# LED-mini20-SHIM.net
KiCad netlist of a schematic drawn in EAGLE
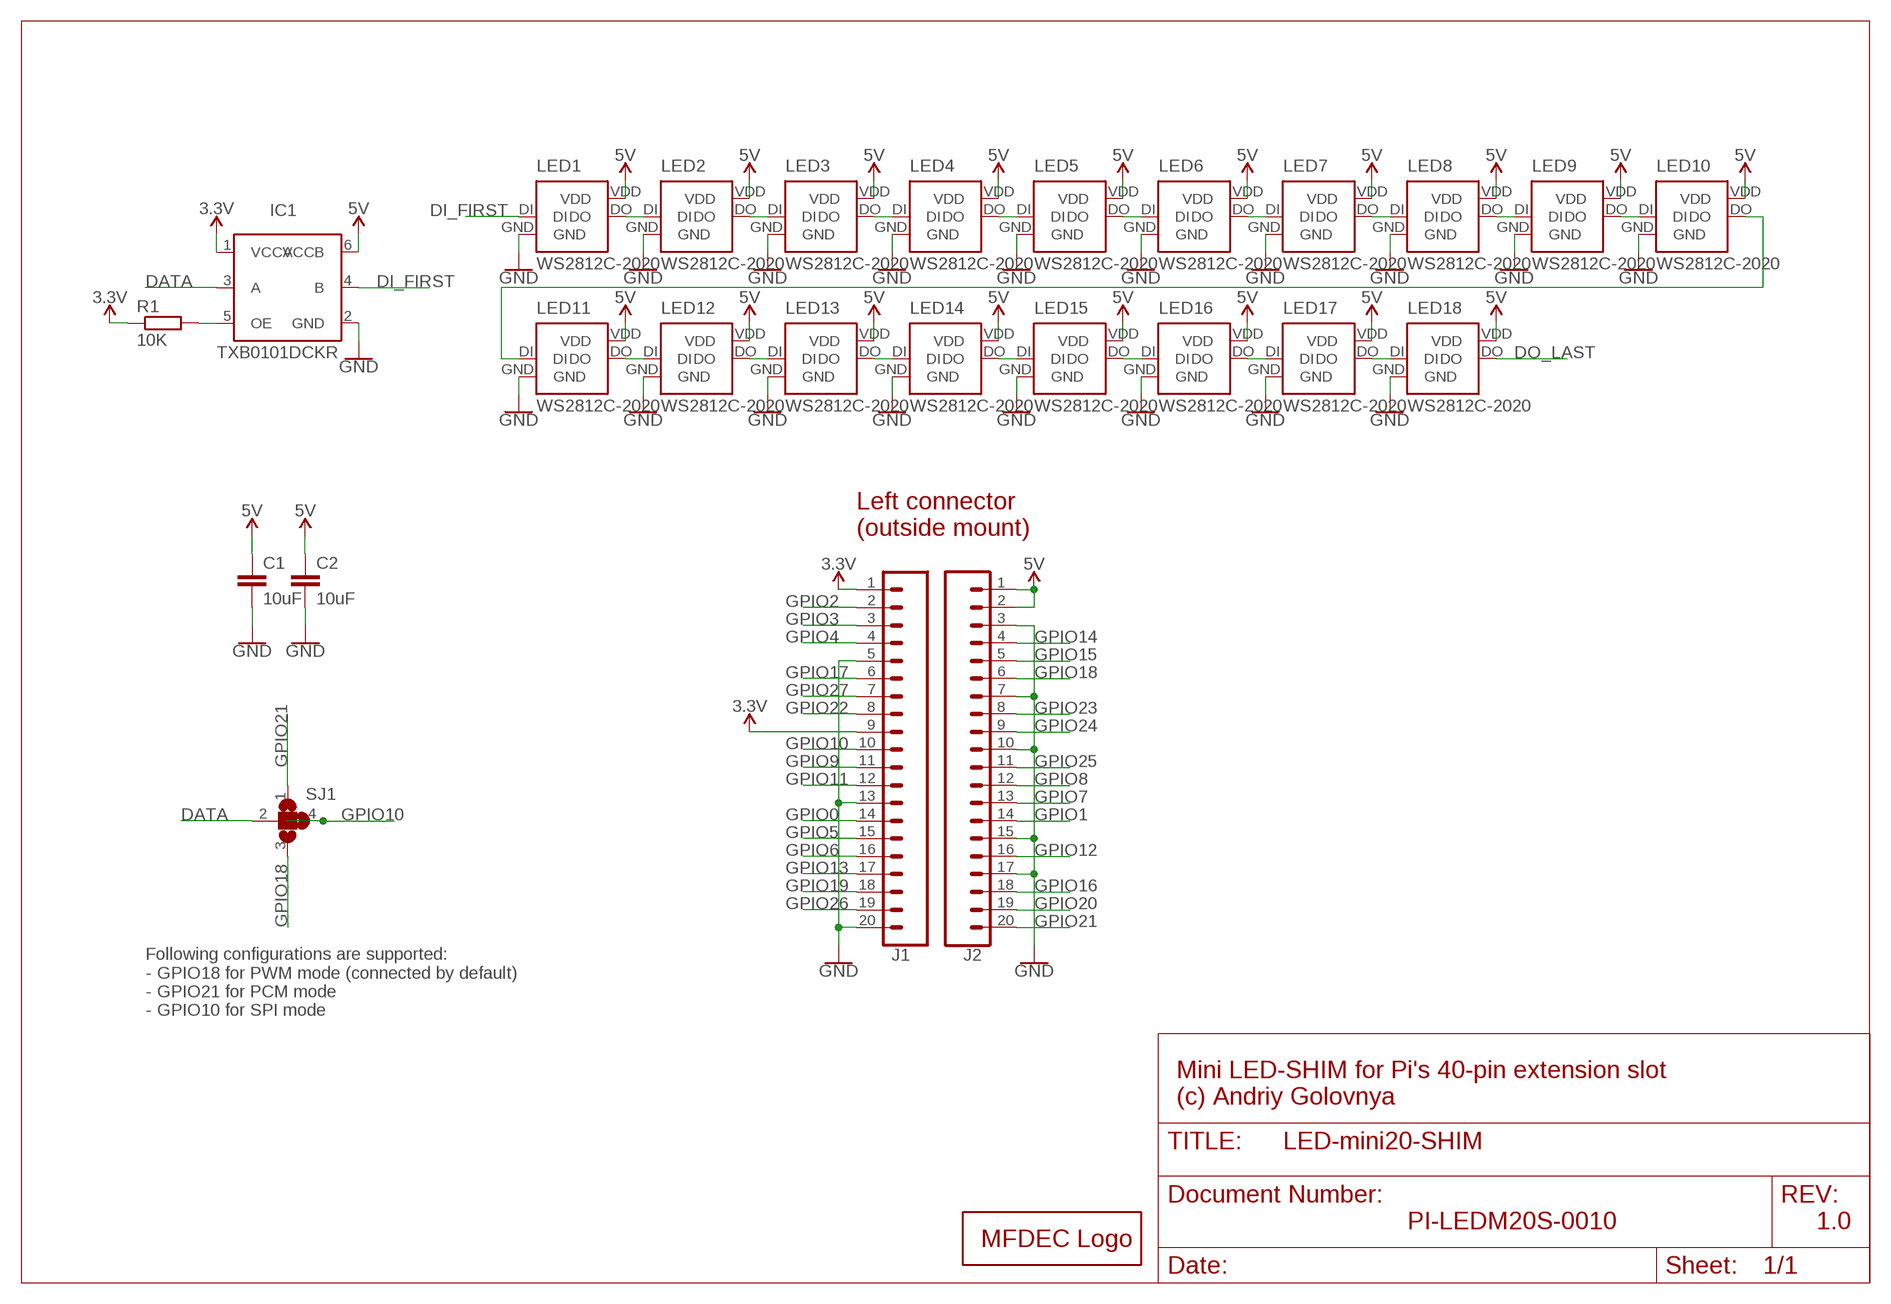
[diagram p0: schematic, sheet 1]

(export (version "E")
  (design (tool "Eeschema 10.0.6"))
  (components
    (comp (ref "C1")
      (value "10uF")
      (footprint "eagle-import:C0805")
      (libsource (lib "eagle-import") (part "C-EUC0805"))
    )
    (comp (ref "C2")
      (value "10uF")
      (footprint "eagle-import:C0805")
      (libsource (lib "eagle-import") (part "C-EUC0805"))
    )
    (comp (ref "IC1")
      (value "TXB0101DCKR")
      (footprint "eagle-import:SOT65P210X110-6N")
      (libsource (lib "eagle-import") (part "TXB0101DCKR"))
    )
    (comp (ref "J1")
      (value "CONN_20LOCK")
      (footprint "eagle-import:1X20_LOCK")
      (libsource (lib "eagle-import") (part "CONN_20LOCK"))
    )
    (comp (ref "J2")
      (value "CONN_20LOCK")
      (footprint "eagle-import:1X20_LOCK")
      (libsource (lib "eagle-import") (part "CONN_20LOCK"))
    )
    (comp (ref "LED1")
      (value "WS2812C-2020")
      (footprint "eagle-import:WS2812X-2020")
      (libsource (lib "eagle-import") (part "WS2812C-2020"))
    )
    (comp (ref "LED2")
      (value "WS2812C-2020")
      (footprint "eagle-import:WS2812X-2020")
      (libsource (lib "eagle-import") (part "WS2812C-2020"))
    )
    (comp (ref "LED3")
      (value "WS2812C-2020")
      (footprint "eagle-import:WS2812X-2020")
      (libsource (lib "eagle-import") (part "WS2812C-2020"))
    )
    (comp (ref "LED4")
      (value "WS2812C-2020")
      (footprint "eagle-import:WS2812X-2020")
      (libsource (lib "eagle-import") (part "WS2812C-2020"))
    )
    (comp (ref "LED5")
      (value "WS2812C-2020")
      (footprint "eagle-import:WS2812X-2020")
      (libsource (lib "eagle-import") (part "WS2812C-2020"))
    )
    (comp (ref "LED6")
      (value "WS2812C-2020")
      (footprint "eagle-import:WS2812X-2020")
      (libsource (lib "eagle-import") (part "WS2812C-2020"))
    )
    (comp (ref "LED7")
      (value "WS2812C-2020")
      (footprint "eagle-import:WS2812X-2020")
      (libsource (lib "eagle-import") (part "WS2812C-2020"))
    )
    (comp (ref "LED8")
      (value "WS2812C-2020")
      (footprint "eagle-import:WS2812X-2020")
      (libsource (lib "eagle-import") (part "WS2812C-2020"))
    )
    (comp (ref "LED9")
      (value "WS2812C-2020")
      (footprint "eagle-import:WS2812X-2020")
      (libsource (lib "eagle-import") (part "WS2812C-2020"))
    )
    (comp (ref "LED10")
      (value "WS2812C-2020")
      (footprint "eagle-import:WS2812X-2020")
      (libsource (lib "eagle-import") (part "WS2812C-2020"))
    )
    (comp (ref "LED11")
      (value "WS2812C-2020")
      (footprint "eagle-import:WS2812X-2020")
      (libsource (lib "eagle-import") (part "WS2812C-2020"))
    )
    (comp (ref "LED12")
      (value "WS2812C-2020")
      (footprint "eagle-import:WS2812X-2020")
      (libsource (lib "eagle-import") (part "WS2812C-2020"))
    )
    (comp (ref "LED13")
      (value "WS2812C-2020")
      (footprint "eagle-import:WS2812X-2020")
      (libsource (lib "eagle-import") (part "WS2812C-2020"))
    )
    (comp (ref "LED14")
      (value "WS2812C-2020")
      (footprint "eagle-import:WS2812X-2020")
      (libsource (lib "eagle-import") (part "WS2812C-2020"))
    )
    (comp (ref "LED15")
      (value "WS2812C-2020")
      (footprint "eagle-import:WS2812X-2020")
      (libsource (lib "eagle-import") (part "WS2812C-2020"))
    )
    (comp (ref "LED16")
      (value "WS2812C-2020")
      (footprint "eagle-import:WS2812X-2020")
      (libsource (lib "eagle-import") (part "WS2812C-2020"))
    )
    (comp (ref "LED17")
      (value "WS2812C-2020")
      (footprint "eagle-import:WS2812X-2020")
      (libsource (lib "eagle-import") (part "WS2812C-2020"))
    )
    (comp (ref "LED18")
      (value "WS2812C-2020")
      (footprint "eagle-import:WS2812X-2020")
      (libsource (lib "eagle-import") (part "WS2812C-2020"))
    )
    (comp (ref "LOGO1")
      (value "MFDECLOGO_L_10MM")
      (footprint "eagle-import:MFDEC_L_10MM")
      (libsource (lib "eagle-import") (part "MFDECLOGO_L_10MM"))
    )
    (comp (ref "R1")
      (value "10K")
      (footprint "eagle-import:R0402")
      (libsource (lib "eagle-import") (part "R-EU_R0402"))
    )
    (comp (ref "SJ1")
      (value "SJ3")
      (footprint "eagle-import:SJ_3")
      (libsource (lib "eagle-import") (part "SJ3"))
    )
  )
  (nets
    (net (code "1") (name "/DATA") (class "Default")
      (node (ref "IC1") (pin "3") (pinfunction "A_3") (pintype "bidirectional"))
      (node (ref "SJ1") (pin "2") (pinfunction "2_2") (pintype "passive"))
    )
    (net (code "2") (name "/DI_FIRST") (class "Default")
      (node (ref "IC1") (pin "4") (pinfunction "B_4") (pintype "bidirectional"))
      (node (ref "LED1") (pin "DI") (pinfunction "DI_DI") (pintype "input"))
    )
    (net (code "3") (name "/DO_LAST") (class "Default")
      (node (ref "LED18") (pin "DO") (pinfunction "DO_DO") (pintype "output"))
    )
    (net (code "4") (name "/GPIO0") (class "Default")
      (node (ref "J1") (pin "14") (pinfunction "14_14") (pintype "passive"))
    )
    (net (code "5") (name "/GPIO1") (class "Default")
      (node (ref "J2") (pin "14") (pinfunction "14_14") (pintype "passive"))
    )
    (net (code "6") (name "/GPIO2") (class "Default")
      (node (ref "J1") (pin "2") (pinfunction "2_2") (pintype "passive"))
    )
    (net (code "7") (name "/GPIO3") (class "Default")
      (node (ref "J1") (pin "3") (pinfunction "3_3") (pintype "passive"))
    )
    (net (code "8") (name "/GPIO4") (class "Default")
      (node (ref "J1") (pin "4") (pinfunction "4_4") (pintype "passive"))
    )
    (net (code "9") (name "/GPIO5") (class "Default")
      (node (ref "J1") (pin "15") (pinfunction "15_15") (pintype "passive"))
    )
    (net (code "10") (name "/GPIO6") (class "Default")
      (node (ref "J1") (pin "16") (pinfunction "16_16") (pintype "passive"))
    )
    (net (code "11") (name "/GPIO7") (class "Default")
      (node (ref "J2") (pin "13") (pinfunction "13_13") (pintype "passive"))
    )
    (net (code "12") (name "/GPIO8") (class "Default")
      (node (ref "J2") (pin "12") (pinfunction "12_12") (pintype "passive"))
    )
    (net (code "13") (name "/GPIO9") (class "Default")
      (node (ref "J1") (pin "11") (pinfunction "11_11") (pintype "passive"))
    )
    (net (code "14") (name "/GPIO10") (class "Default")
      (node (ref "J1") (pin "10") (pinfunction "10_10") (pintype "passive"))
      (node (ref "SJ1") (pin "4") (pinfunction "4_4") (pintype "passive"))
    )
    (net (code "15") (name "/GPIO11") (class "Default")
      (node (ref "J1") (pin "12") (pinfunction "12_12") (pintype "passive"))
    )
    (net (code "16") (name "/GPIO12") (class "Default")
      (node (ref "J2") (pin "16") (pinfunction "16_16") (pintype "passive"))
    )
    (net (code "17") (name "/GPIO13") (class "Default")
      (node (ref "J1") (pin "17") (pinfunction "17_17") (pintype "passive"))
    )
    (net (code "18") (name "/GPIO14") (class "Default")
      (node (ref "J2") (pin "4") (pinfunction "4_4") (pintype "passive"))
    )
    (net (code "19") (name "/GPIO15") (class "Default")
      (node (ref "J2") (pin "5") (pinfunction "5_5") (pintype "passive"))
    )
    (net (code "20") (name "/GPIO16") (class "Default")
      (node (ref "J2") (pin "18") (pinfunction "18_18") (pintype "passive"))
    )
    (net (code "21") (name "/GPIO17") (class "Default")
      (node (ref "J1") (pin "6") (pinfunction "6_6") (pintype "passive"))
    )
    (net (code "22") (name "/GPIO18") (class "Default")
      (node (ref "J2") (pin "6") (pinfunction "6_6") (pintype "passive"))
      (node (ref "SJ1") (pin "3") (pinfunction "3_3") (pintype "passive"))
    )
    (net (code "23") (name "/GPIO19") (class "Default")
      (node (ref "J1") (pin "18") (pinfunction "18_18") (pintype "passive"))
    )
    (net (code "24") (name "/GPIO20") (class "Default")
      (node (ref "J2") (pin "19") (pinfunction "19_19") (pintype "passive"))
    )
    (net (code "25") (name "/GPIO21") (class "Default")
      (node (ref "J2") (pin "20") (pinfunction "20_20") (pintype "passive"))
      (node (ref "SJ1") (pin "1") (pinfunction "1_1") (pintype "passive"))
    )
    (net (code "26") (name "/GPIO22") (class "Default")
      (node (ref "J1") (pin "8") (pinfunction "8_8") (pintype "passive"))
    )
    (net (code "27") (name "/GPIO23") (class "Default")
      (node (ref "J2") (pin "8") (pinfunction "8_8") (pintype "passive"))
    )
    (net (code "28") (name "/GPIO24") (class "Default")
      (node (ref "J2") (pin "9") (pinfunction "9_9") (pintype "passive"))
    )
    (net (code "29") (name "/GPIO25") (class "Default")
      (node (ref "J2") (pin "11") (pinfunction "11_11") (pintype "passive"))
    )
    (net (code "30") (name "/GPIO26") (class "Default")
      (node (ref "J1") (pin "19") (pinfunction "19_19") (pintype "passive"))
    )
    (net (code "31") (name "/GPIO27") (class "Default")
      (node (ref "J1") (pin "7") (pinfunction "7_7") (pintype "passive"))
    )
    (net (code "32") (name "3.3V") (class "Default")
      (node (ref "IC1") (pin "1") (pinfunction "VCCA_1") (pintype "power_in"))
      (node (ref "J1") (pin "1") (pinfunction "1_1") (pintype "passive"))
      (node (ref "J1") (pin "9") (pinfunction "9_9") (pintype "passive"))
      (node (ref "R1") (pin "1") (pinfunction "1_1") (pintype "passive"))
    )
    (net (code "33") (name "5V") (class "Default")
      (node (ref "C1") (pin "1") (pinfunction "1_1") (pintype "passive"))
      (node (ref "C2") (pin "1") (pinfunction "1_1") (pintype "passive"))
      (node (ref "IC1") (pin "6") (pinfunction "VCCB_6") (pintype "power_in"))
      (node (ref "J2") (pin "1") (pinfunction "1_1") (pintype "passive"))
      (node (ref "J2") (pin "2") (pinfunction "2_2") (pintype "passive"))
      (node (ref "LED1") (pin "VDD") (pinfunction "VDD_VDD") (pintype "power_in"))
      (node (ref "LED10") (pin "VDD") (pinfunction "VDD_VDD") (pintype "power_in"))
      (node (ref "LED11") (pin "VDD") (pinfunction "VDD_VDD") (pintype "power_in"))
      (node (ref "LED12") (pin "VDD") (pinfunction "VDD_VDD") (pintype "power_in"))
      (node (ref "LED13") (pin "VDD") (pinfunction "VDD_VDD") (pintype "power_in"))
      (node (ref "LED14") (pin "VDD") (pinfunction "VDD_VDD") (pintype "power_in"))
      (node (ref "LED15") (pin "VDD") (pinfunction "VDD_VDD") (pintype "power_in"))
      (node (ref "LED16") (pin "VDD") (pinfunction "VDD_VDD") (pintype "power_in"))
      (node (ref "LED17") (pin "VDD") (pinfunction "VDD_VDD") (pintype "power_in"))
      (node (ref "LED18") (pin "VDD") (pinfunction "VDD_VDD") (pintype "power_in"))
      (node (ref "LED2") (pin "VDD") (pinfunction "VDD_VDD") (pintype "power_in"))
      (node (ref "LED3") (pin "VDD") (pinfunction "VDD_VDD") (pintype "power_in"))
      (node (ref "LED4") (pin "VDD") (pinfunction "VDD_VDD") (pintype "power_in"))
      (node (ref "LED5") (pin "VDD") (pinfunction "VDD_VDD") (pintype "power_in"))
      (node (ref "LED6") (pin "VDD") (pinfunction "VDD_VDD") (pintype "power_in"))
      (node (ref "LED7") (pin "VDD") (pinfunction "VDD_VDD") (pintype "power_in"))
      (node (ref "LED8") (pin "VDD") (pinfunction "VDD_VDD") (pintype "power_in"))
      (node (ref "LED9") (pin "VDD") (pinfunction "VDD_VDD") (pintype "power_in"))
    )
    (net (code "34") (name "GND") (class "Default")
      (node (ref "C1") (pin "2") (pinfunction "2_2") (pintype "passive"))
      (node (ref "C2") (pin "2") (pinfunction "2_2") (pintype "passive"))
      (node (ref "IC1") (pin "2") (pinfunction "GND_2") (pintype "power_in"))
      (node (ref "J1") (pin "13") (pinfunction "13_13") (pintype "passive"))
      (node (ref "J1") (pin "20") (pinfunction "20_20") (pintype "passive"))
      (node (ref "J1") (pin "5") (pinfunction "5_5") (pintype "passive"))
      (node (ref "J2") (pin "10") (pinfunction "10_10") (pintype "passive"))
      (node (ref "J2") (pin "15") (pinfunction "15_15") (pintype "passive"))
      (node (ref "J2") (pin "17") (pinfunction "17_17") (pintype "passive"))
      (node (ref "J2") (pin "3") (pinfunction "3_3") (pintype "passive"))
      (node (ref "J2") (pin "7") (pinfunction "7_7") (pintype "passive"))
      (node (ref "LED1") (pin "GND") (pinfunction "GND_GND") (pintype "power_in"))
      (node (ref "LED10") (pin "GND") (pinfunction "GND_GND") (pintype "power_in"))
      (node (ref "LED11") (pin "GND") (pinfunction "GND_GND") (pintype "power_in"))
      (node (ref "LED12") (pin "GND") (pinfunction "GND_GND") (pintype "power_in"))
      (node (ref "LED13") (pin "GND") (pinfunction "GND_GND") (pintype "power_in"))
      (node (ref "LED14") (pin "GND") (pinfunction "GND_GND") (pintype "power_in"))
      (node (ref "LED15") (pin "GND") (pinfunction "GND_GND") (pintype "power_in"))
      (node (ref "LED16") (pin "GND") (pinfunction "GND_GND") (pintype "power_in"))
      (node (ref "LED17") (pin "GND") (pinfunction "GND_GND") (pintype "power_in"))
      (node (ref "LED18") (pin "GND") (pinfunction "GND_GND") (pintype "power_in"))
      (node (ref "LED2") (pin "GND") (pinfunction "GND_GND") (pintype "power_in"))
      (node (ref "LED3") (pin "GND") (pinfunction "GND_GND") (pintype "power_in"))
      (node (ref "LED4") (pin "GND") (pinfunction "GND_GND") (pintype "power_in"))
      (node (ref "LED5") (pin "GND") (pinfunction "GND_GND") (pintype "power_in"))
      (node (ref "LED6") (pin "GND") (pinfunction "GND_GND") (pintype "power_in"))
      (node (ref "LED7") (pin "GND") (pinfunction "GND_GND") (pintype "power_in"))
      (node (ref "LED8") (pin "GND") (pinfunction "GND_GND") (pintype "power_in"))
      (node (ref "LED9") (pin "GND") (pinfunction "GND_GND") (pintype "power_in"))
    )
    (net (code "35") (name "Net-(IC1-OE)") (class "Default")
      (node (ref "IC1") (pin "5") (pinfunction "OE_5") (pintype "input"))
      (node (ref "R1") (pin "2") (pinfunction "2_2") (pintype "passive"))
    )
    (net (code "36") (name "Net-(LED1-PadDO)") (class "Default")
      (node (ref "LED1") (pin "DO") (pinfunction "DO_DO") (pintype "output"))
      (node (ref "LED2") (pin "DI") (pinfunction "DI_DI") (pintype "input"))
    )
    (net (code "37") (name "Net-(LED2-PadDO)") (class "Default")
      (node (ref "LED2") (pin "DO") (pinfunction "DO_DO") (pintype "output"))
      (node (ref "LED3") (pin "DI") (pinfunction "DI_DI") (pintype "input"))
    )
    (net (code "38") (name "Net-(LED3-PadDO)") (class "Default")
      (node (ref "LED3") (pin "DO") (pinfunction "DO_DO") (pintype "output"))
      (node (ref "LED4") (pin "DI") (pinfunction "DI_DI") (pintype "input"))
    )
    (net (code "39") (name "Net-(LED4-PadDO)") (class "Default")
      (node (ref "LED4") (pin "DO") (pinfunction "DO_DO") (pintype "output"))
      (node (ref "LED5") (pin "DI") (pinfunction "DI_DI") (pintype "input"))
    )
    (net (code "40") (name "Net-(LED5-PadDO)") (class "Default")
      (node (ref "LED5") (pin "DO") (pinfunction "DO_DO") (pintype "output"))
      (node (ref "LED6") (pin "DI") (pinfunction "DI_DI") (pintype "input"))
    )
    (net (code "41") (name "Net-(LED6-PadDO)") (class "Default")
      (node (ref "LED6") (pin "DO") (pinfunction "DO_DO") (pintype "output"))
      (node (ref "LED7") (pin "DI") (pinfunction "DI_DI") (pintype "input"))
    )
    (net (code "42") (name "Net-(LED7-PadDO)") (class "Default")
      (node (ref "LED7") (pin "DO") (pinfunction "DO_DO") (pintype "output"))
      (node (ref "LED8") (pin "DI") (pinfunction "DI_DI") (pintype "input"))
    )
    (net (code "43") (name "Net-(LED8-PadDO)") (class "Default")
      (node (ref "LED8") (pin "DO") (pinfunction "DO_DO") (pintype "output"))
      (node (ref "LED9") (pin "DI") (pinfunction "DI_DI") (pintype "input"))
    )
    (net (code "44") (name "Net-(LED10-PadDI)") (class "Default")
      (node (ref "LED10") (pin "DI") (pinfunction "DI_DI") (pintype "input"))
      (node (ref "LED9") (pin "DO") (pinfunction "DO_DO") (pintype "output"))
    )
    (net (code "45") (name "Net-(LED10-PadDO)") (class "Default")
      (node (ref "LED10") (pin "DO") (pinfunction "DO_DO") (pintype "output"))
      (node (ref "LED11") (pin "DI") (pinfunction "DI_DI") (pintype "input"))
    )
    (net (code "46") (name "Net-(LED11-PadDO)") (class "Default")
      (node (ref "LED11") (pin "DO") (pinfunction "DO_DO") (pintype "output"))
      (node (ref "LED12") (pin "DI") (pinfunction "DI_DI") (pintype "input"))
    )
    (net (code "47") (name "Net-(LED12-PadDO)") (class "Default")
      (node (ref "LED12") (pin "DO") (pinfunction "DO_DO") (pintype "output"))
      (node (ref "LED13") (pin "DI") (pinfunction "DI_DI") (pintype "input"))
    )
    (net (code "48") (name "Net-(LED13-PadDO)") (class "Default")
      (node (ref "LED13") (pin "DO") (pinfunction "DO_DO") (pintype "output"))
      (node (ref "LED14") (pin "DI") (pinfunction "DI_DI") (pintype "input"))
    )
    (net (code "49") (name "Net-(LED14-PadDO)") (class "Default")
      (node (ref "LED14") (pin "DO") (pinfunction "DO_DO") (pintype "output"))
      (node (ref "LED15") (pin "DI") (pinfunction "DI_DI") (pintype "input"))
    )
    (net (code "50") (name "Net-(LED15-PadDO)") (class "Default")
      (node (ref "LED15") (pin "DO") (pinfunction "DO_DO") (pintype "output"))
      (node (ref "LED16") (pin "DI") (pinfunction "DI_DI") (pintype "input"))
    )
    (net (code "51") (name "Net-(LED16-PadDO)") (class "Default")
      (node (ref "LED16") (pin "DO") (pinfunction "DO_DO") (pintype "output"))
      (node (ref "LED17") (pin "DI") (pinfunction "DI_DI") (pintype "input"))
    )
    (net (code "52") (name "Net-(LED17-PadDO)") (class "Default")
      (node (ref "LED17") (pin "DO") (pinfunction "DO_DO") (pintype "output"))
      (node (ref "LED18") (pin "DI") (pinfunction "DI_DI") (pintype "input"))
    )
  )
)
